# mqtt-LightbulbwithtempandIR.net
KiCad netlist of a schematic drawn in EAGLE
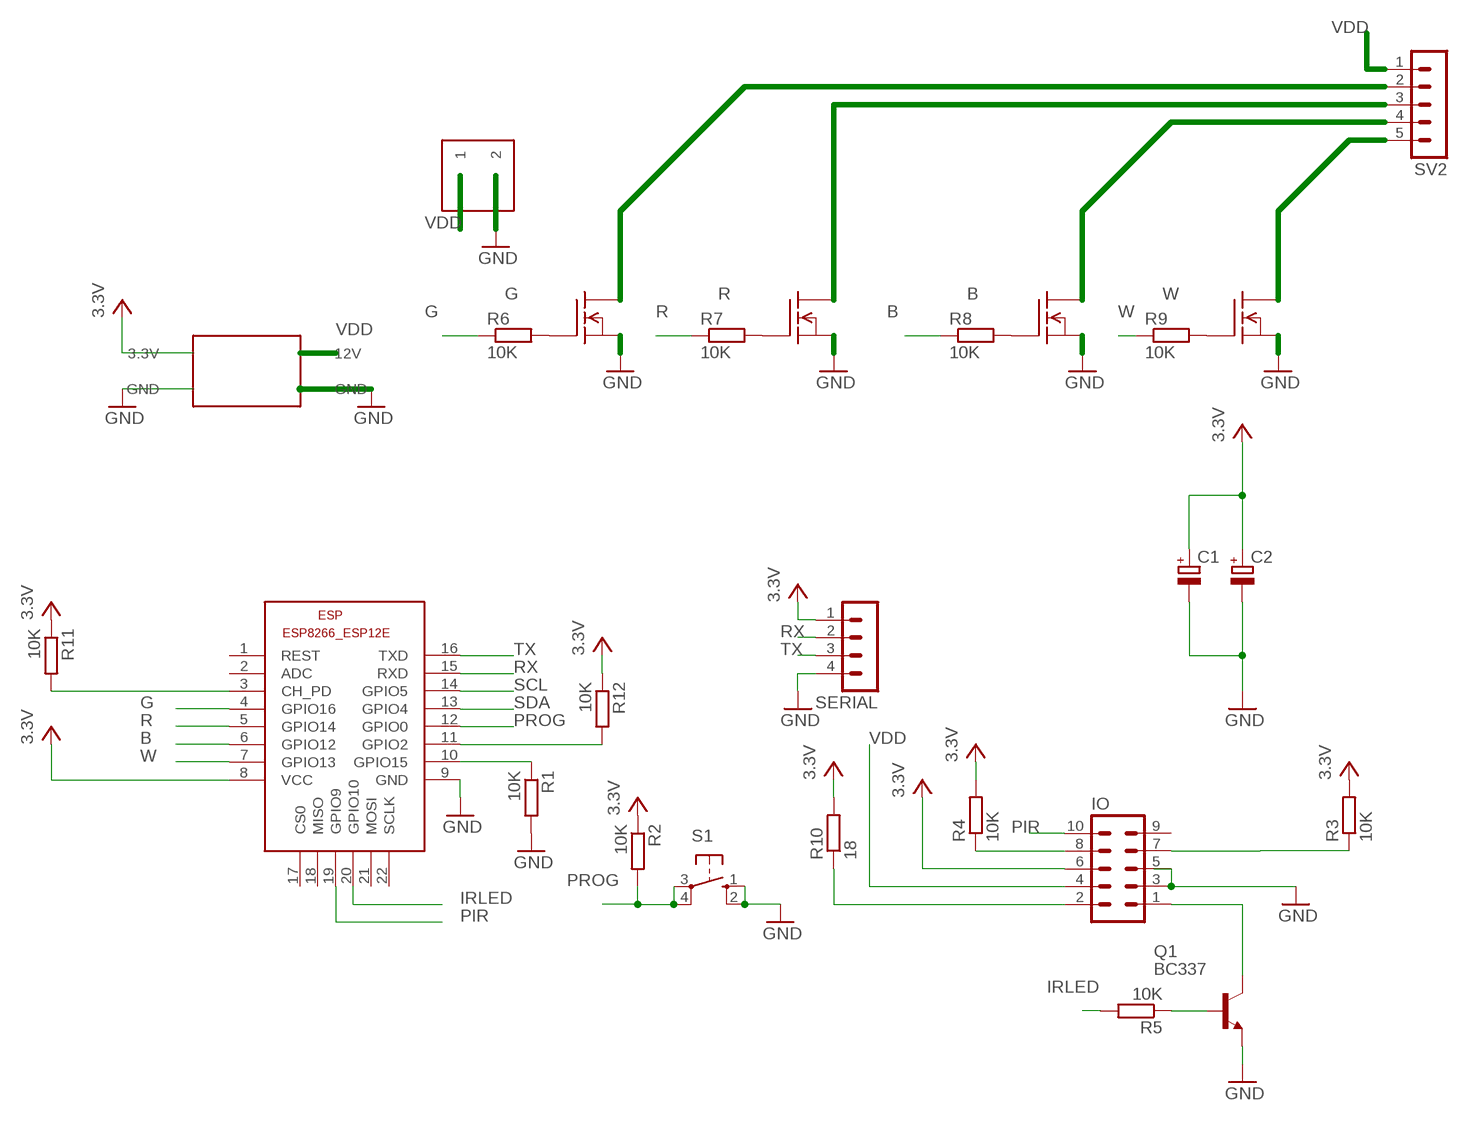
[diagram p0: schematic, sheet 1]

(export (version "E")
  (design (tool "Eeschema 10.0.6"))
  (components
    (comp (ref "B")
      (value "FDS5680")
      (footprint "eagle-import:SO-8")
      (libsource (lib "eagle-import") (part "FDS5680"))
    )
    (comp (ref "C1")
      (value "CPOL-EUE2-5")
      (footprint "eagle-import:E2-5")
      (libsource (lib "eagle-import") (part "CPOL-EUE2-5"))
    )
    (comp (ref "C2")
      (value "CPOL-EUE2-5")
      (footprint "eagle-import:E2-5")
      (libsource (lib "eagle-import") (part "CPOL-EUE2-5"))
    )
    (comp (ref "ESP")
      (value "ESP8266-12EESP8266-ESP12E")
      (footprint "eagle-import:ESP8266-ESP12E")
      (libsource (lib "eagle-import") (part "ESP8266-12EESP8266-ESP12E"))
    )
    (comp (ref "G")
      (value "FDS5680")
      (footprint "eagle-import:SO-8")
      (libsource (lib "eagle-import") (part "FDS5680"))
    )
    (comp (ref "IO")
      (value "MA05-2")
      (footprint "eagle-import:MA05-2")
      (libsource (lib "eagle-import") (part "MA05-2"))
    )
    (comp (ref "PWR1")
      (value "MP2307-MINI-360")
      (footprint "eagle-import:MP2307-MINI-360")
      (libsource (lib "eagle-import") (part "MP2307-MINI-360"))
    )
    (comp (ref "PWR_IN")
      (value "KF350-P2")
      (footprint "eagle-import:KF350-2P")
      (libsource (lib "eagle-import") (part "KF350-P2"))
    )
    (comp (ref "Q1")
      (value "BC337")
      (footprint "eagle-import:TO92")
      (libsource (lib "eagle-import") (part "BC337"))
    )
    (comp (ref "R")
      (value "FDS5680")
      (footprint "eagle-import:SO-8")
      (libsource (lib "eagle-import") (part "FDS5680"))
    )
    (comp (ref "R1")
      (value "10K")
      (footprint "eagle-import:R0603")
      (libsource (lib "eagle-import") (part "R-EU_R0603"))
    )
    (comp (ref "R2")
      (value "10K")
      (footprint "eagle-import:R0603")
      (libsource (lib "eagle-import") (part "R-EU_R0603"))
    )
    (comp (ref "R3")
      (value "10K")
      (footprint "eagle-import:R0603")
      (libsource (lib "eagle-import") (part "R-EU_R0603"))
    )
    (comp (ref "R4")
      (value "10K")
      (footprint "eagle-import:R0603")
      (libsource (lib "eagle-import") (part "R-EU_R0603"))
    )
    (comp (ref "R5")
      (value "10K")
      (footprint "eagle-import:R0603")
      (libsource (lib "eagle-import") (part "R-EU_R0603"))
    )
    (comp (ref "R6")
      (value "10K")
      (footprint "eagle-import:R0603")
      (libsource (lib "eagle-import") (part "R-EU_R0603"))
    )
    (comp (ref "R7")
      (value "10K")
      (footprint "eagle-import:R0603")
      (libsource (lib "eagle-import") (part "R-EU_R0603"))
    )
    (comp (ref "R8")
      (value "10K")
      (footprint "eagle-import:R0603")
      (libsource (lib "eagle-import") (part "R-EU_R0603"))
    )
    (comp (ref "R9")
      (value "10K")
      (footprint "eagle-import:R0603")
      (libsource (lib "eagle-import") (part "R-EU_R0603"))
    )
    (comp (ref "R10")
      (value "18")
      (footprint "eagle-import:R0603")
      (libsource (lib "eagle-import") (part "R-EU_R0603"))
    )
    (comp (ref "R11")
      (value "10K")
      (footprint "eagle-import:R0603")
      (libsource (lib "eagle-import") (part "R-EU_R0603"))
    )
    (comp (ref "R12")
      (value "10K")
      (footprint "eagle-import:R0603")
      (libsource (lib "eagle-import") (part "R-EU_R0603"))
    )
    (comp (ref "S1")
      (value "10-XX")
      (footprint "eagle-import:B3F-10XX")
      (fields (field (name "MPN") "B3F-1000"))
      (libsource (lib "eagle-import") (part "10-XX"))
    )
    (comp (ref "SERIAL")
      (value "MA04-1")
      (footprint "eagle-import:MA04-1")
      (libsource (lib "eagle-import") (part "MA04-1"))
    )
    (comp (ref "SV2")
      (value "MA05-1")
      (footprint "eagle-import:MA05-1")
      (libsource (lib "eagle-import") (part "MA05-1"))
    )
    (comp (ref "W")
      (value "FDS5680")
      (footprint "eagle-import:SO-8")
      (libsource (lib "eagle-import") (part "FDS5680"))
    )
  )
  (nets
    (net (code "1") (name "/B") (class "Default")
      (node (ref "ESP") (pin "6") (pinfunction "GPIO12_6") (pintype "bidirectional"))
      (node (ref "R8") (pin "1") (pinfunction "1_1") (pintype "passive"))
    )
    (net (code "2") (name "/G") (class "Default")
      (node (ref "ESP") (pin "4") (pinfunction "GPIO16_4") (pintype "bidirectional"))
      (node (ref "R6") (pin "1") (pinfunction "1_1") (pintype "passive"))
    )
    (net (code "3") (name "/IRLED") (class "Default")
      (node (ref "ESP") (pin "20") (pinfunction "GPIO10_20") (pintype "bidirectional"))
      (node (ref "R5") (pin "2") (pinfunction "2_2") (pintype "passive"))
    )
    (net (code "4") (name "/PIR") (class "Default")
      (node (ref "ESP") (pin "19") (pinfunction "GPIO9_19") (pintype "bidirectional"))
      (node (ref "IO") (pin "10") (pinfunction "10_10") (pintype "passive"))
    )
    (net (code "5") (name "/PROG") (class "Default")
      (node (ref "ESP") (pin "12") (pinfunction "GPIO0_12") (pintype "bidirectional"))
      (node (ref "R2") (pin "2") (pinfunction "2_2") (pintype "passive"))
      (node (ref "S1") (pin "3") (pinfunction "P_3") (pintype "passive"))
      (node (ref "S1") (pin "4") (pinfunction "P1_4") (pintype "passive"))
    )
    (net (code "6") (name "/R") (class "Default")
      (node (ref "ESP") (pin "5") (pinfunction "GPIO14_5") (pintype "bidirectional"))
      (node (ref "R7") (pin "1") (pinfunction "1_1") (pintype "passive"))
    )
    (net (code "7") (name "/RX") (class "Default")
      (node (ref "ESP") (pin "15") (pinfunction "RXD_15") (pintype "bidirectional"))
      (node (ref "SERIAL") (pin "2") (pinfunction "2_2") (pintype "passive"))
    )
    (net (code "8") (name "/SCL") (class "Default")
      (node (ref "ESP") (pin "14") (pinfunction "GPIO5_14") (pintype "bidirectional"))
      (node (ref "IO") (pin "7") (pinfunction "7_7") (pintype "passive"))
      (node (ref "R3") (pin "1") (pinfunction "1_1") (pintype "passive"))
    )
    (net (code "9") (name "/SDA") (class "Default")
      (node (ref "ESP") (pin "13") (pinfunction "GPIO4_13") (pintype "bidirectional"))
      (node (ref "IO") (pin "8") (pinfunction "8_8") (pintype "passive"))
      (node (ref "R4") (pin "1") (pinfunction "1_1") (pintype "passive"))
    )
    (net (code "10") (name "/TX") (class "Default")
      (node (ref "ESP") (pin "16") (pinfunction "TXD_16") (pintype "bidirectional"))
      (node (ref "SERIAL") (pin "3") (pinfunction "3_3") (pintype "passive"))
    )
    (net (code "11") (name "/VDD") (class "Default")
      (node (ref "IO") (pin "4") (pinfunction "4_4") (pintype "passive"))
      (node (ref "PWR1") (pin "12V") (pinfunction "12V_12V") (pintype "power_in"))
      (node (ref "PWR_IN") (pin "1") (pinfunction "1_1") (pintype "bidirectional"))
      (node (ref "SV2") (pin "1") (pinfunction "1_1") (pintype "passive"))
    )
    (net (code "12") (name "/W") (class "Default")
      (node (ref "ESP") (pin "7") (pinfunction "GPIO13_7") (pintype "bidirectional"))
      (node (ref "R9") (pin "1") (pinfunction "1_1") (pintype "passive"))
    )
    (net (code "13") (name "3.3V") (class "Default")
      (node (ref "C1") (pin "+") (pinfunction "+_+") (pintype "passive"))
      (node (ref "C2") (pin "+") (pinfunction "+_+") (pintype "passive"))
      (node (ref "ESP") (pin "8") (pinfunction "VCC_8") (pintype "bidirectional"))
      (node (ref "IO") (pin "6") (pinfunction "6_6") (pintype "passive"))
      (node (ref "PWR1") (pin "3.3V") (pinfunction "3.3V_3.3V") (pintype "power_in"))
      (node (ref "R10") (pin "2") (pinfunction "2_2") (pintype "passive"))
      (node (ref "R11") (pin "1") (pinfunction "1_1") (pintype "passive"))
      (node (ref "R12") (pin "1") (pinfunction "1_1") (pintype "passive"))
      (node (ref "R2") (pin "1") (pinfunction "1_1") (pintype "passive"))
      (node (ref "R3") (pin "2") (pinfunction "2_2") (pintype "passive"))
      (node (ref "R4") (pin "2") (pinfunction "2_2") (pintype "passive"))
      (node (ref "SERIAL") (pin "1") (pinfunction "1_1") (pintype "passive"))
    )
    (net (code "14") (name "GND") (class "Default")
      (node (ref "B") (pin "1") (pinfunction "S_1") (pintype "passive"))
      (node (ref "B") (pin "2") (pinfunction "S_2") (pintype "passive"))
      (node (ref "B") (pin "3") (pinfunction "S_3") (pintype "passive"))
      (node (ref "C1") (pin "-") (pinfunction "-_-") (pintype "passive"))
      (node (ref "C2") (pin "-") (pinfunction "-_-") (pintype "passive"))
      (node (ref "ESP") (pin "9") (pinfunction "GND_9") (pintype "bidirectional"))
      (node (ref "G") (pin "1") (pinfunction "S_1") (pintype "passive"))
      (node (ref "G") (pin "2") (pinfunction "S_2") (pintype "passive"))
      (node (ref "G") (pin "3") (pinfunction "S_3") (pintype "passive"))
      (node (ref "IO") (pin "3") (pinfunction "3_3") (pintype "passive"))
      (node (ref "IO") (pin "5") (pinfunction "5_5") (pintype "passive"))
      (node (ref "PWR1") (pin "GND@1") (pinfunction "GND_GND@1") (pintype "power_in"))
      (node (ref "PWR1") (pin "GND@2") (pinfunction "GND_GND@2") (pintype "power_in"))
      (node (ref "PWR_IN") (pin "2") (pinfunction "2_2") (pintype "bidirectional"))
      (node (ref "Q1") (pin "1") (pinfunction "E_1") (pintype "passive"))
      (node (ref "R") (pin "1") (pinfunction "S_1") (pintype "passive"))
      (node (ref "R") (pin "2") (pinfunction "S_2") (pintype "passive"))
      (node (ref "R") (pin "3") (pinfunction "S_3") (pintype "passive"))
      (node (ref "R1") (pin "2") (pinfunction "2_2") (pintype "passive"))
      (node (ref "S1") (pin "1") (pinfunction "S_1") (pintype "passive"))
      (node (ref "S1") (pin "2") (pinfunction "S1_2") (pintype "passive"))
      (node (ref "SERIAL") (pin "4") (pinfunction "4_4") (pintype "passive"))
      (node (ref "W") (pin "1") (pinfunction "S_1") (pintype "passive"))
      (node (ref "W") (pin "2") (pinfunction "S_2") (pintype "passive"))
      (node (ref "W") (pin "3") (pinfunction "S_3") (pintype "passive"))
    )
    (net (code "15") (name "Net-(B-D-Pad5)") (class "Default")
      (node (ref "B") (pin "5") (pinfunction "D_5") (pintype "passive"))
      (node (ref "B") (pin "6") (pinfunction "D_6") (pintype "passive"))
      (node (ref "B") (pin "7") (pinfunction "D_7") (pintype "passive"))
      (node (ref "B") (pin "8") (pinfunction "D_8") (pintype "passive"))
      (node (ref "SV2") (pin "4") (pinfunction "4_4") (pintype "passive"))
    )
    (net (code "16") (name "Net-(B-G)") (class "Default")
      (node (ref "B") (pin "4") (pinfunction "G_4") (pintype "passive"))
      (node (ref "R8") (pin "2") (pinfunction "2_2") (pintype "passive"))
    )
    (net (code "17") (name "Net-(ESP-CH_PD)") (class "Default")
      (node (ref "ESP") (pin "3") (pinfunction "CH_PD_3") (pintype "bidirectional"))
      (node (ref "R11") (pin "2") (pinfunction "2_2") (pintype "passive"))
    )
    (net (code "18") (name "Net-(ESP-GPIO2)") (class "Default")
      (node (ref "ESP") (pin "11") (pinfunction "GPIO2_11") (pintype "bidirectional"))
      (node (ref "R12") (pin "2") (pinfunction "2_2") (pintype "passive"))
    )
    (net (code "19") (name "Net-(ESP-GPIO15)") (class "Default")
      (node (ref "ESP") (pin "10") (pinfunction "GPIO15_10") (pintype "bidirectional"))
      (node (ref "R1") (pin "1") (pinfunction "1_1") (pintype "passive"))
    )
    (net (code "20") (name "Net-(G-D-Pad5)") (class "Default")
      (node (ref "G") (pin "5") (pinfunction "D_5") (pintype "passive"))
      (node (ref "G") (pin "6") (pinfunction "D_6") (pintype "passive"))
      (node (ref "G") (pin "7") (pinfunction "D_7") (pintype "passive"))
      (node (ref "G") (pin "8") (pinfunction "D_8") (pintype "passive"))
      (node (ref "SV2") (pin "2") (pinfunction "2_2") (pintype "passive"))
    )
    (net (code "21") (name "Net-(G-G)") (class "Default")
      (node (ref "G") (pin "4") (pinfunction "G_4") (pintype "passive"))
      (node (ref "R6") (pin "2") (pinfunction "2_2") (pintype "passive"))
    )
    (net (code "22") (name "Net-(IO-Pad2)") (class "Default")
      (node (ref "IO") (pin "2") (pinfunction "2_2") (pintype "passive"))
      (node (ref "R10") (pin "1") (pinfunction "1_1") (pintype "passive"))
    )
    (net (code "23") (name "Net-(Q1-B)") (class "Default")
      (node (ref "Q1") (pin "2") (pinfunction "B_2") (pintype "passive"))
      (node (ref "R5") (pin "1") (pinfunction "1_1") (pintype "passive"))
    )
    (net (code "24") (name "Net-(Q1-C)") (class "Default")
      (node (ref "IO") (pin "1") (pinfunction "1_1") (pintype "passive"))
      (node (ref "Q1") (pin "3") (pinfunction "C_3") (pintype "passive"))
    )
    (net (code "25") (name "Net-(R-D-Pad5)") (class "Default")
      (node (ref "R") (pin "5") (pinfunction "D_5") (pintype "passive"))
      (node (ref "R") (pin "6") (pinfunction "D_6") (pintype "passive"))
      (node (ref "R") (pin "7") (pinfunction "D_7") (pintype "passive"))
      (node (ref "R") (pin "8") (pinfunction "D_8") (pintype "passive"))
      (node (ref "SV2") (pin "3") (pinfunction "3_3") (pintype "passive"))
    )
    (net (code "26") (name "Net-(R-G)") (class "Default")
      (node (ref "R") (pin "4") (pinfunction "G_4") (pintype "passive"))
      (node (ref "R7") (pin "2") (pinfunction "2_2") (pintype "passive"))
    )
    (net (code "27") (name "Net-(SV2-Pad5)") (class "Default")
      (node (ref "SV2") (pin "5") (pinfunction "5_5") (pintype "passive"))
      (node (ref "W") (pin "5") (pinfunction "D_5") (pintype "passive"))
      (node (ref "W") (pin "6") (pinfunction "D_6") (pintype "passive"))
      (node (ref "W") (pin "7") (pinfunction "D_7") (pintype "passive"))
      (node (ref "W") (pin "8") (pinfunction "D_8") (pintype "passive"))
    )
    (net (code "28") (name "Net-(W-G)") (class "Default")
      (node (ref "R9") (pin "2") (pinfunction "2_2") (pintype "passive"))
      (node (ref "W") (pin "4") (pinfunction "G_4") (pintype "passive"))
    )
    (net (code "29") (name "unconnected-(ESP-ADC-Pad2)") (class "Default")
      (node (ref "ESP") (pin "2") (pinfunction "ADC_2") (pintype "bidirectional"))
    )
    (net (code "30") (name "unconnected-(ESP-CS0-Pad17)") (class "Default")
      (node (ref "ESP") (pin "17") (pinfunction "CS0_17") (pintype "bidirectional"))
    )
    (net (code "31") (name "unconnected-(ESP-MISO-Pad18)") (class "Default")
      (node (ref "ESP") (pin "18") (pinfunction "MISO_18") (pintype "bidirectional"))
    )
    (net (code "32") (name "unconnected-(ESP-MOSI-Pad21)") (class "Default")
      (node (ref "ESP") (pin "21") (pinfunction "MOSI_21") (pintype "bidirectional"))
    )
    (net (code "33") (name "unconnected-(ESP-REST-Pad1)") (class "Default")
      (node (ref "ESP") (pin "1") (pinfunction "REST_1") (pintype "bidirectional"))
    )
    (net (code "34") (name "unconnected-(ESP-SCLK-Pad22)") (class "Default")
      (node (ref "ESP") (pin "22") (pinfunction "SCLK_22") (pintype "bidirectional"))
    )
    (net (code "35") (name "unconnected-(IO-Pad9)") (class "Default")
      (node (ref "IO") (pin "9") (pinfunction "9_9") (pintype "passive"))
    )
  )
)
